# G848M.net
KiCad netlist of a schematic drawn in EAGLE
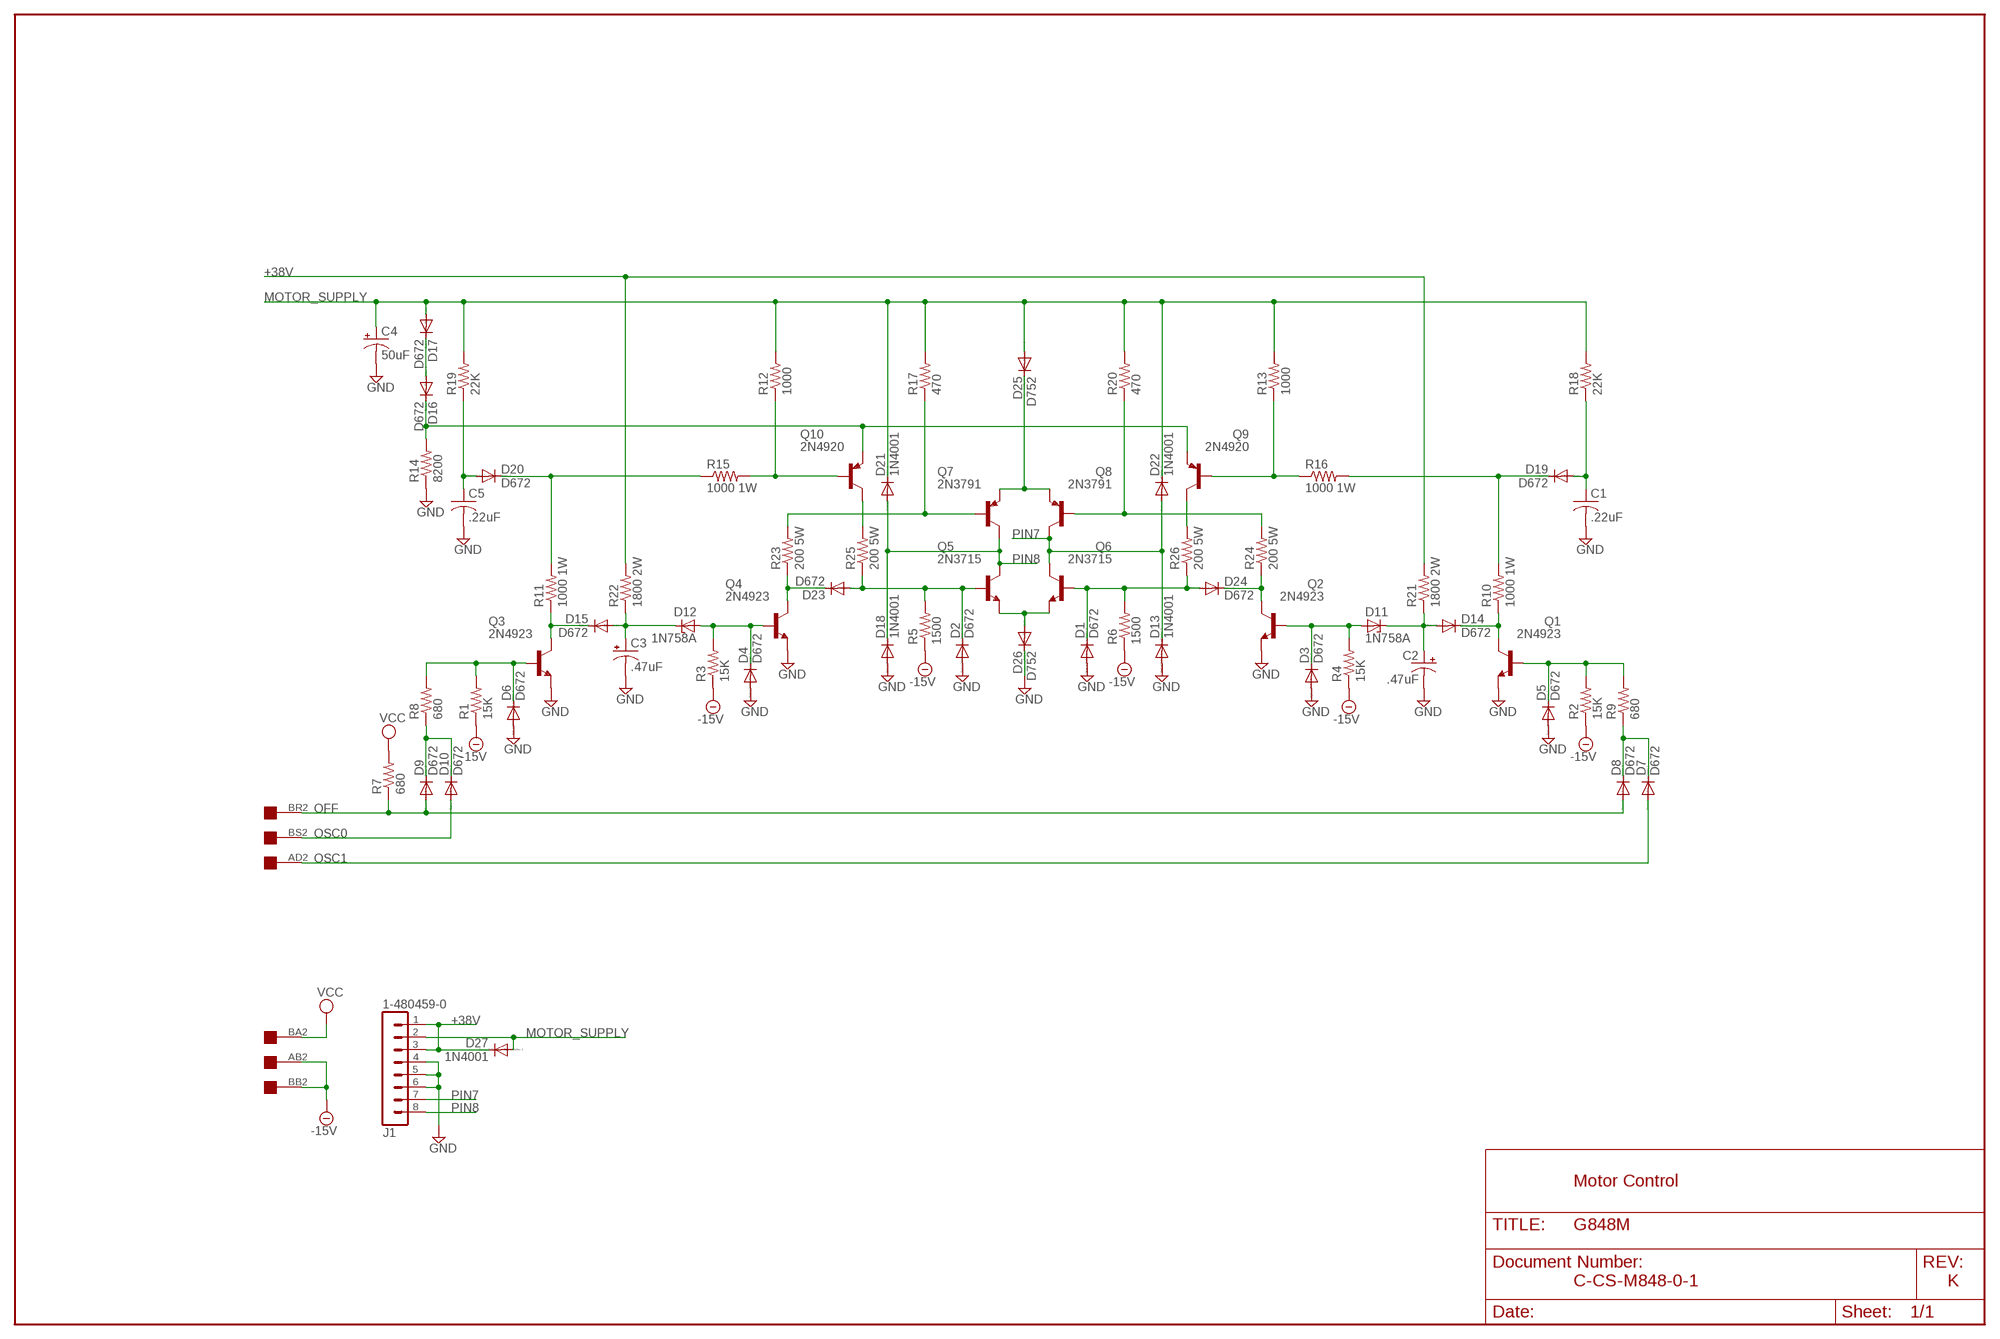
[diagram p0: schematic, sheet 1]

(export (version "E")
  (design (tool "Eeschema 10.0.6"))
  (components
    (comp (ref "C1")
      (value ".22uF")
      (footprint "eagle-import:C325-137X374")
      (libsource (lib "eagle-import") (part "C-US325-137X374"))
    )
    (comp (ref "C2")
      (value ".47uF")
      (footprint "eagle-import:E15-5")
      (libsource (lib "eagle-import") (part "CPOL-USE15-5AXIAL"))
    )
    (comp (ref "C3")
      (value ".47uF")
      (footprint "eagle-import:E15-5")
      (libsource (lib "eagle-import") (part "CPOL-USE15-5AXIAL"))
    )
    (comp (ref "C4")
      (value "50uF")
      (footprint "eagle-import:E30-10")
      (libsource (lib "eagle-import") (part "CPOL-USE30-10AXIAL"))
    )
    (comp (ref "C5")
      (value ".22uF")
      (footprint "eagle-import:C325-137X374")
      (libsource (lib "eagle-import") (part "C-US325-137X374"))
    )
    (comp (ref "D1")
      (value "D672")
      (footprint "eagle-import:DO35-10")
      (libsource (lib "eagle-import") (part "DIODE-DO35-10"))
    )
    (comp (ref "D2")
      (value "D672")
      (footprint "eagle-import:DO35-10")
      (libsource (lib "eagle-import") (part "DIODE-DO35-10"))
    )
    (comp (ref "D3")
      (value "D672")
      (footprint "eagle-import:DO35-10")
      (libsource (lib "eagle-import") (part "DIODE-DO35-10"))
    )
    (comp (ref "D4")
      (value "D672")
      (footprint "eagle-import:DO35-10")
      (libsource (lib "eagle-import") (part "DIODE-DO35-10"))
    )
    (comp (ref "D5")
      (value "D672")
      (footprint "eagle-import:DO35-10")
      (libsource (lib "eagle-import") (part "DIODE-DO35-10"))
    )
    (comp (ref "D6")
      (value "D672")
      (footprint "eagle-import:DO35-10")
      (libsource (lib "eagle-import") (part "DIODE-DO35-10"))
    )
    (comp (ref "D7")
      (value "D672")
      (footprint "eagle-import:DO35-10")
      (libsource (lib "eagle-import") (part "DIODE-DO35-10"))
    )
    (comp (ref "D8")
      (value "D672")
      (footprint "eagle-import:DO35-10")
      (libsource (lib "eagle-import") (part "DIODE-DO35-10"))
    )
    (comp (ref "D9")
      (value "D672")
      (footprint "eagle-import:DO35-10")
      (libsource (lib "eagle-import") (part "DIODE-DO35-10"))
    )
    (comp (ref "D10")
      (value "D672")
      (footprint "eagle-import:DO35-10")
      (libsource (lib "eagle-import") (part "DIODE-DO35-10"))
    )
    (comp (ref "D11")
      (value "1N758A")
      (footprint "eagle-import:DO35Z10")
      (libsource (lib "eagle-import") (part "ZENER-DIODEDO35Z10"))
    )
    (comp (ref "D12")
      (value "1N758A")
      (footprint "eagle-import:DO35Z10")
      (libsource (lib "eagle-import") (part "ZENER-DIODEDO35Z10"))
    )
    (comp (ref "D13")
      (value "1N4001")
      (footprint "eagle-import:DO41-10")
      (libsource (lib "eagle-import") (part "1N4004"))
    )
    (comp (ref "D14")
      (value "D672")
      (footprint "eagle-import:DO35-10")
      (libsource (lib "eagle-import") (part "DIODE-DO35-10"))
    )
    (comp (ref "D15")
      (value "D672")
      (footprint "eagle-import:DO35-10")
      (libsource (lib "eagle-import") (part "DIODE-DO35-10"))
    )
    (comp (ref "D16")
      (value "D672")
      (footprint "eagle-import:DO35-10")
      (libsource (lib "eagle-import") (part "DIODE-DO35-10"))
    )
    (comp (ref "D17")
      (value "D672")
      (footprint "eagle-import:DO35-10")
      (libsource (lib "eagle-import") (part "DIODE-DO35-10"))
    )
    (comp (ref "D18")
      (value "1N4001")
      (footprint "eagle-import:DO41-10")
      (libsource (lib "eagle-import") (part "1N4004"))
    )
    (comp (ref "D19")
      (value "D672")
      (footprint "eagle-import:DO35-10")
      (libsource (lib "eagle-import") (part "DIODE-DO35-10"))
    )
    (comp (ref "D20")
      (value "D672")
      (footprint "eagle-import:DO35-10")
      (libsource (lib "eagle-import") (part "DIODE-DO35-10"))
    )
    (comp (ref "D21")
      (value "1N4001")
      (footprint "eagle-import:DO41-10")
      (libsource (lib "eagle-import") (part "1N4004"))
    )
    (comp (ref "D22")
      (value "1N4001")
      (footprint "eagle-import:DO41-10")
      (libsource (lib "eagle-import") (part "1N4004"))
    )
    (comp (ref "D23")
      (value "D672")
      (footprint "eagle-import:DO35-10")
      (libsource (lib "eagle-import") (part "DIODE-DO35-10"))
    )
    (comp (ref "D24")
      (value "D672")
      (footprint "eagle-import:DO35-10")
      (libsource (lib "eagle-import") (part "DIODE-DO35-10"))
    )
    (comp (ref "D25")
      (value "D752")
      (footprint "eagle-import:G4-12")
      (libsource (lib "eagle-import") (part "DIODE-G4-12"))
    )
    (comp (ref "D26")
      (value "D752")
      (footprint "eagle-import:G4-12")
      (libsource (lib "eagle-import") (part "DIODE-G4-12"))
    )
    (comp (ref "D27")
      (value "1N4001")
      (footprint "eagle-import:DO41-10")
      (libsource (lib "eagle-import") (part "1N4004"))
    )
    (comp (ref "J1")
      (value "1-480459-0")
      (footprint "eagle-import:1-480459-0")
      (libsource (lib "eagle-import") (part "1-480459-0"))
    )
    (comp (ref "Q1")
      (value "2N4923")
      (footprint "eagle-import:TO225AHH")
      (libsource (lib "eagle-import") (part "-NPN-TO225HH"))
    )
    (comp (ref "Q2")
      (value "2N4923")
      (footprint "eagle-import:TO225AHH")
      (libsource (lib "eagle-import") (part "-NPN-TO225HH"))
    )
    (comp (ref "Q3")
      (value "2N4923")
      (footprint "eagle-import:TO225AHH")
      (libsource (lib "eagle-import") (part "-NPN-TO225HH"))
    )
    (comp (ref "Q4")
      (value "2N4923")
      (footprint "eagle-import:TO225AHH")
      (libsource (lib "eagle-import") (part "-NPN-TO225HH"))
    )
    (comp (ref "Q5")
      (value "2N3715")
      (footprint "eagle-import:TO3")
      (libsource (lib "eagle-import") (part "-NPN-TO3/"))
    )
    (comp (ref "Q6")
      (value "2N3715")
      (footprint "eagle-import:TO3")
      (libsource (lib "eagle-import") (part "-NPN-TO3/"))
    )
    (comp (ref "Q7")
      (value "2N3791")
      (footprint "eagle-import:TO3")
      (libsource (lib "eagle-import") (part "-PNP-TO3"))
    )
    (comp (ref "Q8")
      (value "2N3791")
      (footprint "eagle-import:TO3")
      (libsource (lib "eagle-import") (part "-PNP-TO3"))
    )
    (comp (ref "Q9")
      (value "2N4920")
      (footprint "eagle-import:TO225AHH")
      (libsource (lib "eagle-import") (part "-PNP-TO225HH"))
    )
    (comp (ref "Q10")
      (value "2N4920")
      (footprint "eagle-import:TO225AHH")
      (libsource (lib "eagle-import") (part "-PNP-TO225HH"))
    )
    (comp (ref "R1")
      (value "15K")
      (footprint "eagle-import:0207_10")
      (libsource (lib "eagle-import") (part "R-US_0207/10"))
    )
    (comp (ref "R2")
      (value "15K")
      (footprint "eagle-import:0207_10")
      (libsource (lib "eagle-import") (part "R-US_0207/10"))
    )
    (comp (ref "R3")
      (value "15K")
      (footprint "eagle-import:0207_10")
      (libsource (lib "eagle-import") (part "R-US_0207/10"))
    )
    (comp (ref "R4")
      (value "15K")
      (footprint "eagle-import:0207_10")
      (libsource (lib "eagle-import") (part "R-US_0207/10"))
    )
    (comp (ref "R5")
      (value "1500")
      (footprint "eagle-import:0207_10")
      (libsource (lib "eagle-import") (part "R-US_0207/10"))
    )
    (comp (ref "R6")
      (value "1500")
      (footprint "eagle-import:0207_10")
      (libsource (lib "eagle-import") (part "R-US_0207/10"))
    )
    (comp (ref "R7")
      (value "680")
      (footprint "eagle-import:0207_10")
      (libsource (lib "eagle-import") (part "R-US_0207/10"))
    )
    (comp (ref "R8")
      (value "680")
      (footprint "eagle-import:0207_10")
      (libsource (lib "eagle-import") (part "R-US_0207/10"))
    )
    (comp (ref "R9")
      (value "680")
      (footprint "eagle-import:0207_10")
      (libsource (lib "eagle-import") (part "R-US_0207/10"))
    )
    (comp (ref "R10")
      (value "1000 1W")
      (footprint "eagle-import:0414_20")
      (libsource (lib "eagle-import") (part "R-US_0414/20"))
    )
    (comp (ref "R11")
      (value "1000 1W")
      (footprint "eagle-import:0414_20")
      (libsource (lib "eagle-import") (part "R-US_0414/20"))
    )
    (comp (ref "R12")
      (value "1000")
      (footprint "eagle-import:0207_10")
      (libsource (lib "eagle-import") (part "R-US_0207/10"))
    )
    (comp (ref "R13")
      (value "1000")
      (footprint "eagle-import:0207_10")
      (libsource (lib "eagle-import") (part "R-US_0207/10"))
    )
    (comp (ref "R14")
      (value "8200")
      (footprint "eagle-import:0207_10")
      (libsource (lib "eagle-import") (part "R-US_0207/10"))
    )
    (comp (ref "R15")
      (value "1000 1W")
      (footprint "eagle-import:0414_20")
      (libsource (lib "eagle-import") (part "R-US_0414/20"))
    )
    (comp (ref "R16")
      (value "1000 1W")
      (footprint "eagle-import:0414_20")
      (libsource (lib "eagle-import") (part "R-US_0414/20"))
    )
    (comp (ref "R17")
      (value "470")
      (footprint "eagle-import:0207_10")
      (libsource (lib "eagle-import") (part "R-US_0207/10"))
    )
    (comp (ref "R18")
      (value "22K")
      (footprint "eagle-import:0207_10")
      (libsource (lib "eagle-import") (part "R-US_0207/10"))
    )
    (comp (ref "R19")
      (value "22K")
      (footprint "eagle-import:0207_10")
      (libsource (lib "eagle-import") (part "R-US_0207/10"))
    )
    (comp (ref "R20")
      (value "470")
      (footprint "eagle-import:0207_10")
      (libsource (lib "eagle-import") (part "R-US_0207/10"))
    )
    (comp (ref "R21")
      (value "1800 2W")
      (footprint "eagle-import:0818_25")
      (libsource (lib "eagle-import") (part "R-US_0818/25"))
    )
    (comp (ref "R22")
      (value "1800 2W")
      (footprint "eagle-import:0818_25")
      (libsource (lib "eagle-import") (part "R-US_0818/25"))
    )
    (comp (ref "R23")
      (value "200 5W")
      (footprint "eagle-import:VTA54")
      (libsource (lib "eagle-import") (part "R-US_VTA54"))
    )
    (comp (ref "R24")
      (value "200 5W")
      (footprint "eagle-import:VTA54")
      (libsource (lib "eagle-import") (part "R-US_VTA54"))
    )
    (comp (ref "R25")
      (value "200 5W")
      (footprint "eagle-import:VTA54")
      (libsource (lib "eagle-import") (part "R-US_VTA54"))
    )
    (comp (ref "R26")
      (value "200 5W")
      (footprint "eagle-import:VTA54")
      (libsource (lib "eagle-import") (part "R-US_VTA54"))
    )
    (comp (ref "U$1")
      (value "DOUBLE")
      (footprint "eagle-import:EDGE-CON4")
      (libsource (lib "eagle-import") (part "DOUBLE"))
    )
  )
  (nets
    (net (code "1") (name "-15V") (class "Default")
      (node (ref "R1") (pin "1") (pinfunction "1_1") (pintype "passive"))
      (node (ref "R2") (pin "1") (pinfunction "1_1") (pintype "passive"))
      (node (ref "R3") (pin "1") (pinfunction "1_1") (pintype "passive"))
      (node (ref "R4") (pin "1") (pinfunction "1_1") (pintype "passive"))
      (node (ref "R5") (pin "1") (pinfunction "1_1") (pintype "passive"))
      (node (ref "R6") (pin "1") (pinfunction "1_1") (pintype "passive"))
      (node (ref "U$1") (pin "AB2") (pinfunction "1_AB2") (pintype "bidirectional"))
      (node (ref "U$1") (pin "BB2") (pinfunction "1_BB2") (pintype "bidirectional"))
    )
    (net (code "2") (name "/+38V") (class "Default")
      (node (ref "D27") (pin "C") (pinfunction "C_C") (pintype "passive"))
      (node (ref "J1") (pin "1") (pinfunction "1_1") (pintype "passive"))
      (node (ref "J1") (pin "3") (pinfunction "3_3") (pintype "passive"))
      (node (ref "R21") (pin "2") (pinfunction "2_2") (pintype "passive"))
      (node (ref "R22") (pin "2") (pinfunction "2_2") (pintype "passive"))
    )
    (net (code "3") (name "/MOTOR_SUPPLY") (class "Default")
      (node (ref "C4") (pin "+") (pinfunction "+_+") (pintype "passive"))
      (node (ref "D17") (pin "A") (pinfunction "A_A") (pintype "passive"))
      (node (ref "D21") (pin "C") (pinfunction "C_C") (pintype "passive"))
      (node (ref "D22") (pin "C") (pinfunction "C_C") (pintype "passive"))
      (node (ref "D25") (pin "A") (pinfunction "A_A") (pintype "passive"))
      (node (ref "D27") (pin "A") (pinfunction "A_A") (pintype "passive"))
      (node (ref "J1") (pin "2") (pinfunction "2_2") (pintype "passive"))
      (node (ref "R12") (pin "2") (pinfunction "2_2") (pintype "passive"))
      (node (ref "R13") (pin "2") (pinfunction "2_2") (pintype "passive"))
      (node (ref "R17") (pin "2") (pinfunction "2_2") (pintype "passive"))
      (node (ref "R18") (pin "2") (pinfunction "2_2") (pintype "passive"))
      (node (ref "R19") (pin "2") (pinfunction "2_2") (pintype "passive"))
      (node (ref "R20") (pin "2") (pinfunction "2_2") (pintype "passive"))
    )
    (net (code "4") (name "/OFF") (class "Default")
      (node (ref "D8") (pin "A") (pinfunction "A_A") (pintype "passive"))
      (node (ref "D9") (pin "A") (pinfunction "A_A") (pintype "passive"))
      (node (ref "R7") (pin "1") (pinfunction "1_1") (pintype "passive"))
      (node (ref "U$1") (pin "BR2") (pinfunction "1_BR2") (pintype "bidirectional"))
    )
    (net (code "5") (name "/OSC0") (class "Default")
      (node (ref "D10") (pin "A") (pinfunction "A_A") (pintype "passive"))
      (node (ref "U$1") (pin "BS2") (pinfunction "1_BS2") (pintype "bidirectional"))
    )
    (net (code "6") (name "/OSC1") (class "Default")
      (node (ref "D7") (pin "A") (pinfunction "A_A") (pintype "passive"))
      (node (ref "U$1") (pin "AD2") (pinfunction "1_AD2") (pintype "bidirectional"))
    )
    (net (code "7") (name "/PIN7") (class "Default")
      (node (ref "D13") (pin "C") (pinfunction "C_C") (pintype "passive"))
      (node (ref "D22") (pin "A") (pinfunction "A_A") (pintype "passive"))
      (node (ref "J1") (pin "7") (pinfunction "7_7") (pintype "passive"))
      (node (ref "Q6") (pin "C") (pinfunction "C_C") (pintype "passive"))
      (node (ref "Q6") (pin "C/") (pinfunction "C_C/") (pintype "passive"))
      (node (ref "Q8") (pin "C") (pinfunction "C_C") (pintype "passive"))
      (node (ref "Q8") (pin "C/") (pinfunction "C_C/") (pintype "passive"))
    )
    (net (code "8") (name "/PIN8") (class "Default")
      (node (ref "D18") (pin "C") (pinfunction "C_C") (pintype "passive"))
      (node (ref "D21") (pin "A") (pinfunction "A_A") (pintype "passive"))
      (node (ref "J1") (pin "8") (pinfunction "8_8") (pintype "passive"))
      (node (ref "Q5") (pin "C") (pinfunction "C_C") (pintype "passive"))
      (node (ref "Q5") (pin "C/") (pinfunction "C_C/") (pintype "passive"))
      (node (ref "Q7") (pin "C") (pinfunction "C_C") (pintype "passive"))
      (node (ref "Q7") (pin "C/") (pinfunction "C_C/") (pintype "passive"))
    )
    (net (code "9") (name "GND") (class "Default")
      (node (ref "C1") (pin "2") (pinfunction "2_2") (pintype "passive"))
      (node (ref "C2") (pin "-") (pinfunction "-_-") (pintype "passive"))
      (node (ref "C3") (pin "-") (pinfunction "-_-") (pintype "passive"))
      (node (ref "C4") (pin "-") (pinfunction "-_-") (pintype "passive"))
      (node (ref "C5") (pin "2") (pinfunction "2_2") (pintype "passive"))
      (node (ref "D1") (pin "A") (pinfunction "A_A") (pintype "passive"))
      (node (ref "D13") (pin "A") (pinfunction "A_A") (pintype "passive"))
      (node (ref "D18") (pin "A") (pinfunction "A_A") (pintype "passive"))
      (node (ref "D2") (pin "A") (pinfunction "A_A") (pintype "passive"))
      (node (ref "D26") (pin "C") (pinfunction "C_C") (pintype "passive"))
      (node (ref "D3") (pin "A") (pinfunction "A_A") (pintype "passive"))
      (node (ref "D4") (pin "A") (pinfunction "A_A") (pintype "passive"))
      (node (ref "D5") (pin "A") (pinfunction "A_A") (pintype "passive"))
      (node (ref "D6") (pin "A") (pinfunction "A_A") (pintype "passive"))
      (node (ref "J1") (pin "4") (pinfunction "4_4") (pintype "passive"))
      (node (ref "J1") (pin "5") (pinfunction "5_5") (pintype "passive"))
      (node (ref "J1") (pin "6") (pinfunction "6_6") (pintype "passive"))
      (node (ref "Q1") (pin "1") (pinfunction "E_1") (pintype "passive"))
      (node (ref "Q2") (pin "1") (pinfunction "E_1") (pintype "passive"))
      (node (ref "Q3") (pin "1") (pinfunction "E_1") (pintype "passive"))
      (node (ref "Q4") (pin "1") (pinfunction "E_1") (pintype "passive"))
      (node (ref "R14") (pin "1") (pinfunction "1_1") (pintype "passive"))
    )
    (net (code "10") (name "Net-(C1-Pad1)") (class "Default")
      (node (ref "C1") (pin "1") (pinfunction "1_1") (pintype "passive"))
      (node (ref "D19") (pin "A") (pinfunction "A_A") (pintype "passive"))
      (node (ref "R18") (pin "1") (pinfunction "1_1") (pintype "passive"))
    )
    (net (code "11") (name "Net-(C2-Pad+)") (class "Default")
      (node (ref "C2") (pin "+") (pinfunction "+_+") (pintype "passive"))
      (node (ref "D11") (pin "C") (pinfunction "C_C") (pintype "passive"))
      (node (ref "D14") (pin "A") (pinfunction "A_A") (pintype "passive"))
      (node (ref "R21") (pin "1") (pinfunction "1_1") (pintype "passive"))
    )
    (net (code "12") (name "Net-(C3-Pad+)") (class "Default")
      (node (ref "C3") (pin "+") (pinfunction "+_+") (pintype "passive"))
      (node (ref "D12") (pin "C") (pinfunction "C_C") (pintype "passive"))
      (node (ref "D15") (pin "A") (pinfunction "A_A") (pintype "passive"))
      (node (ref "R22") (pin "1") (pinfunction "1_1") (pintype "passive"))
    )
    (net (code "13") (name "Net-(C5-Pad1)") (class "Default")
      (node (ref "C5") (pin "1") (pinfunction "1_1") (pintype "passive"))
      (node (ref "D20") (pin "A") (pinfunction "A_A") (pintype "passive"))
      (node (ref "R19") (pin "1") (pinfunction "1_1") (pintype "passive"))
    )
    (net (code "14") (name "Net-(D1-PadC)") (class "Default")
      (node (ref "D1") (pin "C") (pinfunction "C_C") (pintype "passive"))
      (node (ref "D24") (pin "A") (pinfunction "A_A") (pintype "passive"))
      (node (ref "Q6") (pin "B") (pinfunction "B_B") (pintype "passive"))
      (node (ref "R26") (pin "1") (pinfunction "1_1") (pintype "passive"))
      (node (ref "R6") (pin "2") (pinfunction "2_2") (pintype "passive"))
    )
    (net (code "15") (name "Net-(D2-PadC)") (class "Default")
      (node (ref "D2") (pin "C") (pinfunction "C_C") (pintype "passive"))
      (node (ref "D23") (pin "A") (pinfunction "A_A") (pintype "passive"))
      (node (ref "Q5") (pin "B") (pinfunction "B_B") (pintype "passive"))
      (node (ref "R25") (pin "1") (pinfunction "1_1") (pintype "passive"))
      (node (ref "R5") (pin "2") (pinfunction "2_2") (pintype "passive"))
    )
    (net (code "16") (name "Net-(D7-PadC)") (class "Default")
      (node (ref "D7") (pin "C") (pinfunction "C_C") (pintype "passive"))
      (node (ref "D8") (pin "C") (pinfunction "C_C") (pintype "passive"))
      (node (ref "R9") (pin "1") (pinfunction "1_1") (pintype "passive"))
    )
    (net (code "17") (name "Net-(D10-PadC)") (class "Default")
      (node (ref "D10") (pin "C") (pinfunction "C_C") (pintype "passive"))
      (node (ref "D9") (pin "C") (pinfunction "C_C") (pintype "passive"))
      (node (ref "R8") (pin "1") (pinfunction "1_1") (pintype "passive"))
    )
    (net (code "18") (name "Net-(D16-PadA)") (class "Default")
      (node (ref "D16") (pin "A") (pinfunction "A_A") (pintype "passive"))
      (node (ref "D17") (pin "C") (pinfunction "C_C") (pintype "passive"))
    )
    (net (code "19") (name "Net-(D19-PadC)") (class "Default")
      (node (ref "D19") (pin "C") (pinfunction "C_C") (pintype "passive"))
      (node (ref "R10") (pin "2") (pinfunction "2_2") (pintype "passive"))
      (node (ref "R16") (pin "2") (pinfunction "2_2") (pintype "passive"))
    )
    (net (code "20") (name "Net-(D20-PadC)") (class "Default")
      (node (ref "D20") (pin "C") (pinfunction "C_C") (pintype "passive"))
      (node (ref "R11") (pin "2") (pinfunction "2_2") (pintype "passive"))
      (node (ref "R15") (pin "1") (pinfunction "1_1") (pintype "passive"))
    )
    (net (code "21") (name "Net-(D25-PadC)") (class "Default")
      (node (ref "D25") (pin "C") (pinfunction "C_C") (pintype "passive"))
      (node (ref "Q7") (pin "E") (pinfunction "E_E") (pintype "passive"))
      (node (ref "Q8") (pin "E") (pinfunction "E_E") (pintype "passive"))
    )
    (net (code "22") (name "Net-(D26-PadA)") (class "Default")
      (node (ref "D26") (pin "A") (pinfunction "A_A") (pintype "passive"))
      (node (ref "Q5") (pin "E") (pinfunction "E_E") (pintype "passive"))
      (node (ref "Q6") (pin "E") (pinfunction "E_E") (pintype "passive"))
    )
    (net (code "23") (name "Net-(Q1-B)") (class "Default")
      (node (ref "D5") (pin "C") (pinfunction "C_C") (pintype "passive"))
      (node (ref "Q1") (pin "3") (pinfunction "B_3") (pintype "passive"))
      (node (ref "R2") (pin "2") (pinfunction "2_2") (pintype "passive"))
      (node (ref "R9") (pin "2") (pinfunction "2_2") (pintype "passive"))
    )
    (net (code "24") (name "Net-(Q1-C)") (class "Default")
      (node (ref "D14") (pin "C") (pinfunction "C_C") (pintype "passive"))
      (node (ref "Q1") (pin "2") (pinfunction "C_2") (pintype "passive"))
      (node (ref "R10") (pin "1") (pinfunction "1_1") (pintype "passive"))
    )
    (net (code "25") (name "Net-(Q2-B)") (class "Default")
      (node (ref "D11") (pin "A") (pinfunction "A_A") (pintype "passive"))
      (node (ref "D3") (pin "C") (pinfunction "C_C") (pintype "passive"))
      (node (ref "Q2") (pin "3") (pinfunction "B_3") (pintype "passive"))
      (node (ref "R4") (pin "2") (pinfunction "2_2") (pintype "passive"))
    )
    (net (code "26") (name "Net-(Q2-C)") (class "Default")
      (node (ref "D24") (pin "C") (pinfunction "C_C") (pintype "passive"))
      (node (ref "Q2") (pin "2") (pinfunction "C_2") (pintype "passive"))
      (node (ref "R24") (pin "1") (pinfunction "1_1") (pintype "passive"))
    )
    (net (code "27") (name "Net-(Q3-B)") (class "Default")
      (node (ref "D6") (pin "C") (pinfunction "C_C") (pintype "passive"))
      (node (ref "Q3") (pin "3") (pinfunction "B_3") (pintype "passive"))
      (node (ref "R1") (pin "2") (pinfunction "2_2") (pintype "passive"))
      (node (ref "R8") (pin "2") (pinfunction "2_2") (pintype "passive"))
    )
    (net (code "28") (name "Net-(Q3-C)") (class "Default")
      (node (ref "D15") (pin "C") (pinfunction "C_C") (pintype "passive"))
      (node (ref "Q3") (pin "2") (pinfunction "C_2") (pintype "passive"))
      (node (ref "R11") (pin "1") (pinfunction "1_1") (pintype "passive"))
    )
    (net (code "29") (name "Net-(Q4-B)") (class "Default")
      (node (ref "D12") (pin "A") (pinfunction "A_A") (pintype "passive"))
      (node (ref "D4") (pin "C") (pinfunction "C_C") (pintype "passive"))
      (node (ref "Q4") (pin "3") (pinfunction "B_3") (pintype "passive"))
      (node (ref "R3") (pin "2") (pinfunction "2_2") (pintype "passive"))
    )
    (net (code "30") (name "Net-(Q4-C)") (class "Default")
      (node (ref "D23") (pin "C") (pinfunction "C_C") (pintype "passive"))
      (node (ref "Q4") (pin "2") (pinfunction "C_2") (pintype "passive"))
      (node (ref "R23") (pin "1") (pinfunction "1_1") (pintype "passive"))
    )
    (net (code "31") (name "Net-(Q7-PadB)") (class "Default")
      (node (ref "Q7") (pin "B") (pinfunction "B_B") (pintype "passive"))
      (node (ref "R17") (pin "1") (pinfunction "1_1") (pintype "passive"))
      (node (ref "R23") (pin "2") (pinfunction "2_2") (pintype "passive"))
    )
    (net (code "32") (name "Net-(Q8-PadB)") (class "Default")
      (node (ref "Q8") (pin "B") (pinfunction "B_B") (pintype "passive"))
      (node (ref "R20") (pin "1") (pinfunction "1_1") (pintype "passive"))
      (node (ref "R24") (pin "2") (pinfunction "2_2") (pintype "passive"))
    )
    (net (code "33") (name "Net-(Q9-B)") (class "Default")
      (node (ref "Q9") (pin "3") (pinfunction "B_3") (pintype "passive"))
      (node (ref "R13") (pin "1") (pinfunction "1_1") (pintype "passive"))
      (node (ref "R16") (pin "1") (pinfunction "1_1") (pintype "passive"))
    )
    (net (code "34") (name "Net-(Q9-C)") (class "Default")
      (node (ref "Q9") (pin "2") (pinfunction "C_2") (pintype "passive"))
      (node (ref "R26") (pin "2") (pinfunction "2_2") (pintype "passive"))
    )
    (net (code "35") (name "Net-(Q10-B)") (class "Default")
      (node (ref "Q10") (pin "3") (pinfunction "B_3") (pintype "passive"))
      (node (ref "R12") (pin "1") (pinfunction "1_1") (pintype "passive"))
      (node (ref "R15") (pin "2") (pinfunction "2_2") (pintype "passive"))
    )
    (net (code "36") (name "Net-(Q10-C)") (class "Default")
      (node (ref "Q10") (pin "2") (pinfunction "C_2") (pintype "passive"))
      (node (ref "R25") (pin "2") (pinfunction "2_2") (pintype "passive"))
    )
    (net (code "37") (name "Net-(Q10-E)") (class "Default")
      (node (ref "D16") (pin "C") (pinfunction "C_C") (pintype "passive"))
      (node (ref "Q10") (pin "1") (pinfunction "E_1") (pintype "passive"))
      (node (ref "Q9") (pin "1") (pinfunction "E_1") (pintype "passive"))
      (node (ref "R14") (pin "2") (pinfunction "2_2") (pintype "passive"))
    )
    (net (code "38") (name "VCC") (class "Default")
      (node (ref "R7") (pin "2") (pinfunction "2_2") (pintype "passive"))
      (node (ref "U$1") (pin "BA2") (pinfunction "1_BA2") (pintype "bidirectional"))
    )
  )
)
